# 1A20J14_1A21J12_A.net
KiCad netlist of a schematic drawn in Altium Designer
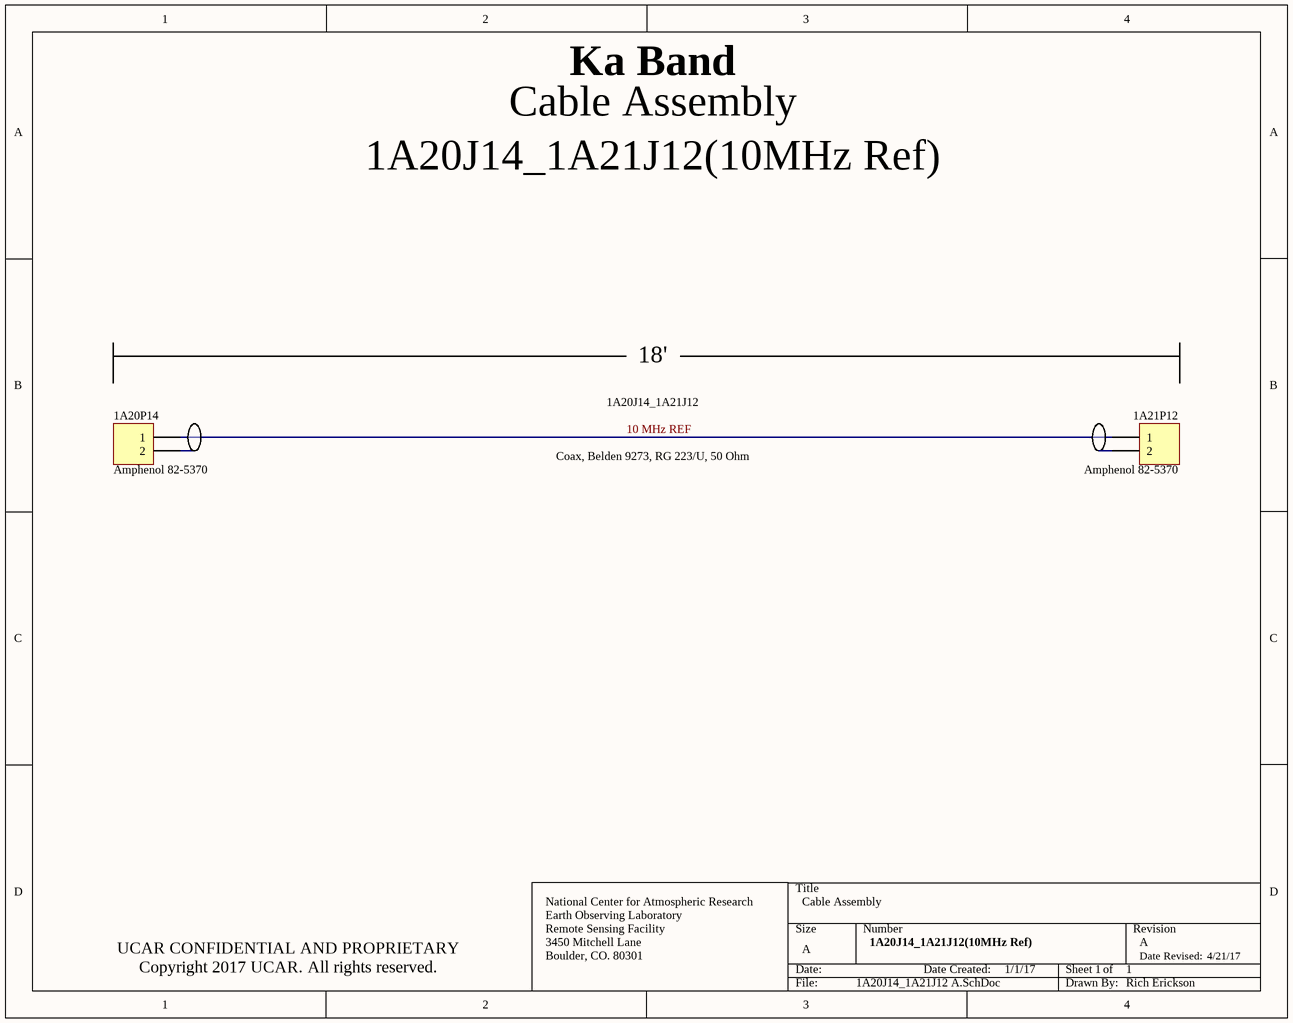
[diagram p0: 1A20J14_1A21J12 A.SchDoc]

(export (version "E")
  (design (tool "Eeschema 10.0.6"))
  (components
    (comp (ref "1A20P14")
      (value "Amphenol 82-5370")
      (footprint "HDR1X2")
      (description "Header, 2-Pin")
      (fields (field (name "PUBLISHER") "Altium Limited"))
      (libsource (lib "") (part "Header 2_1"))
    )
    (comp (ref "1A21P12")
      (value "Amphenol 82-5370")
      (footprint "HDR1X2")
      (description "Header, 2-Pin")
      (fields (field (name "PUBLISHER") "Altium Limited"))
      (libsource (lib "Miscellaneous Connectors") (part "Header 2"))
    )
  )
  (nets
    (net (code "1") (name "/10 MHz REF") (class "Default")
      (node (ref "1A20P14") (pin "1") (pinfunction "1_1") (pintype "passive"))
      (node (ref "1A21P12") (pin "1") (pinfunction "1_1") (pintype "passive"))
    )
    (net (code "2") (name "unconnected-(1A20P14-Pad2)") (class "Default")
      (node (ref "1A20P14") (pin "2") (pinfunction "2_2") (pintype "passive"))
    )
    (net (code "3") (name "unconnected-(1A21P12-Pad2)") (class "Default")
      (node (ref "1A21P12") (pin "2") (pinfunction "2_2") (pintype "passive"))
    )
  )
)
